# DS90UB933TRTVRQ1.net
KiCad netlist of a schematic drawn in Altium Designer
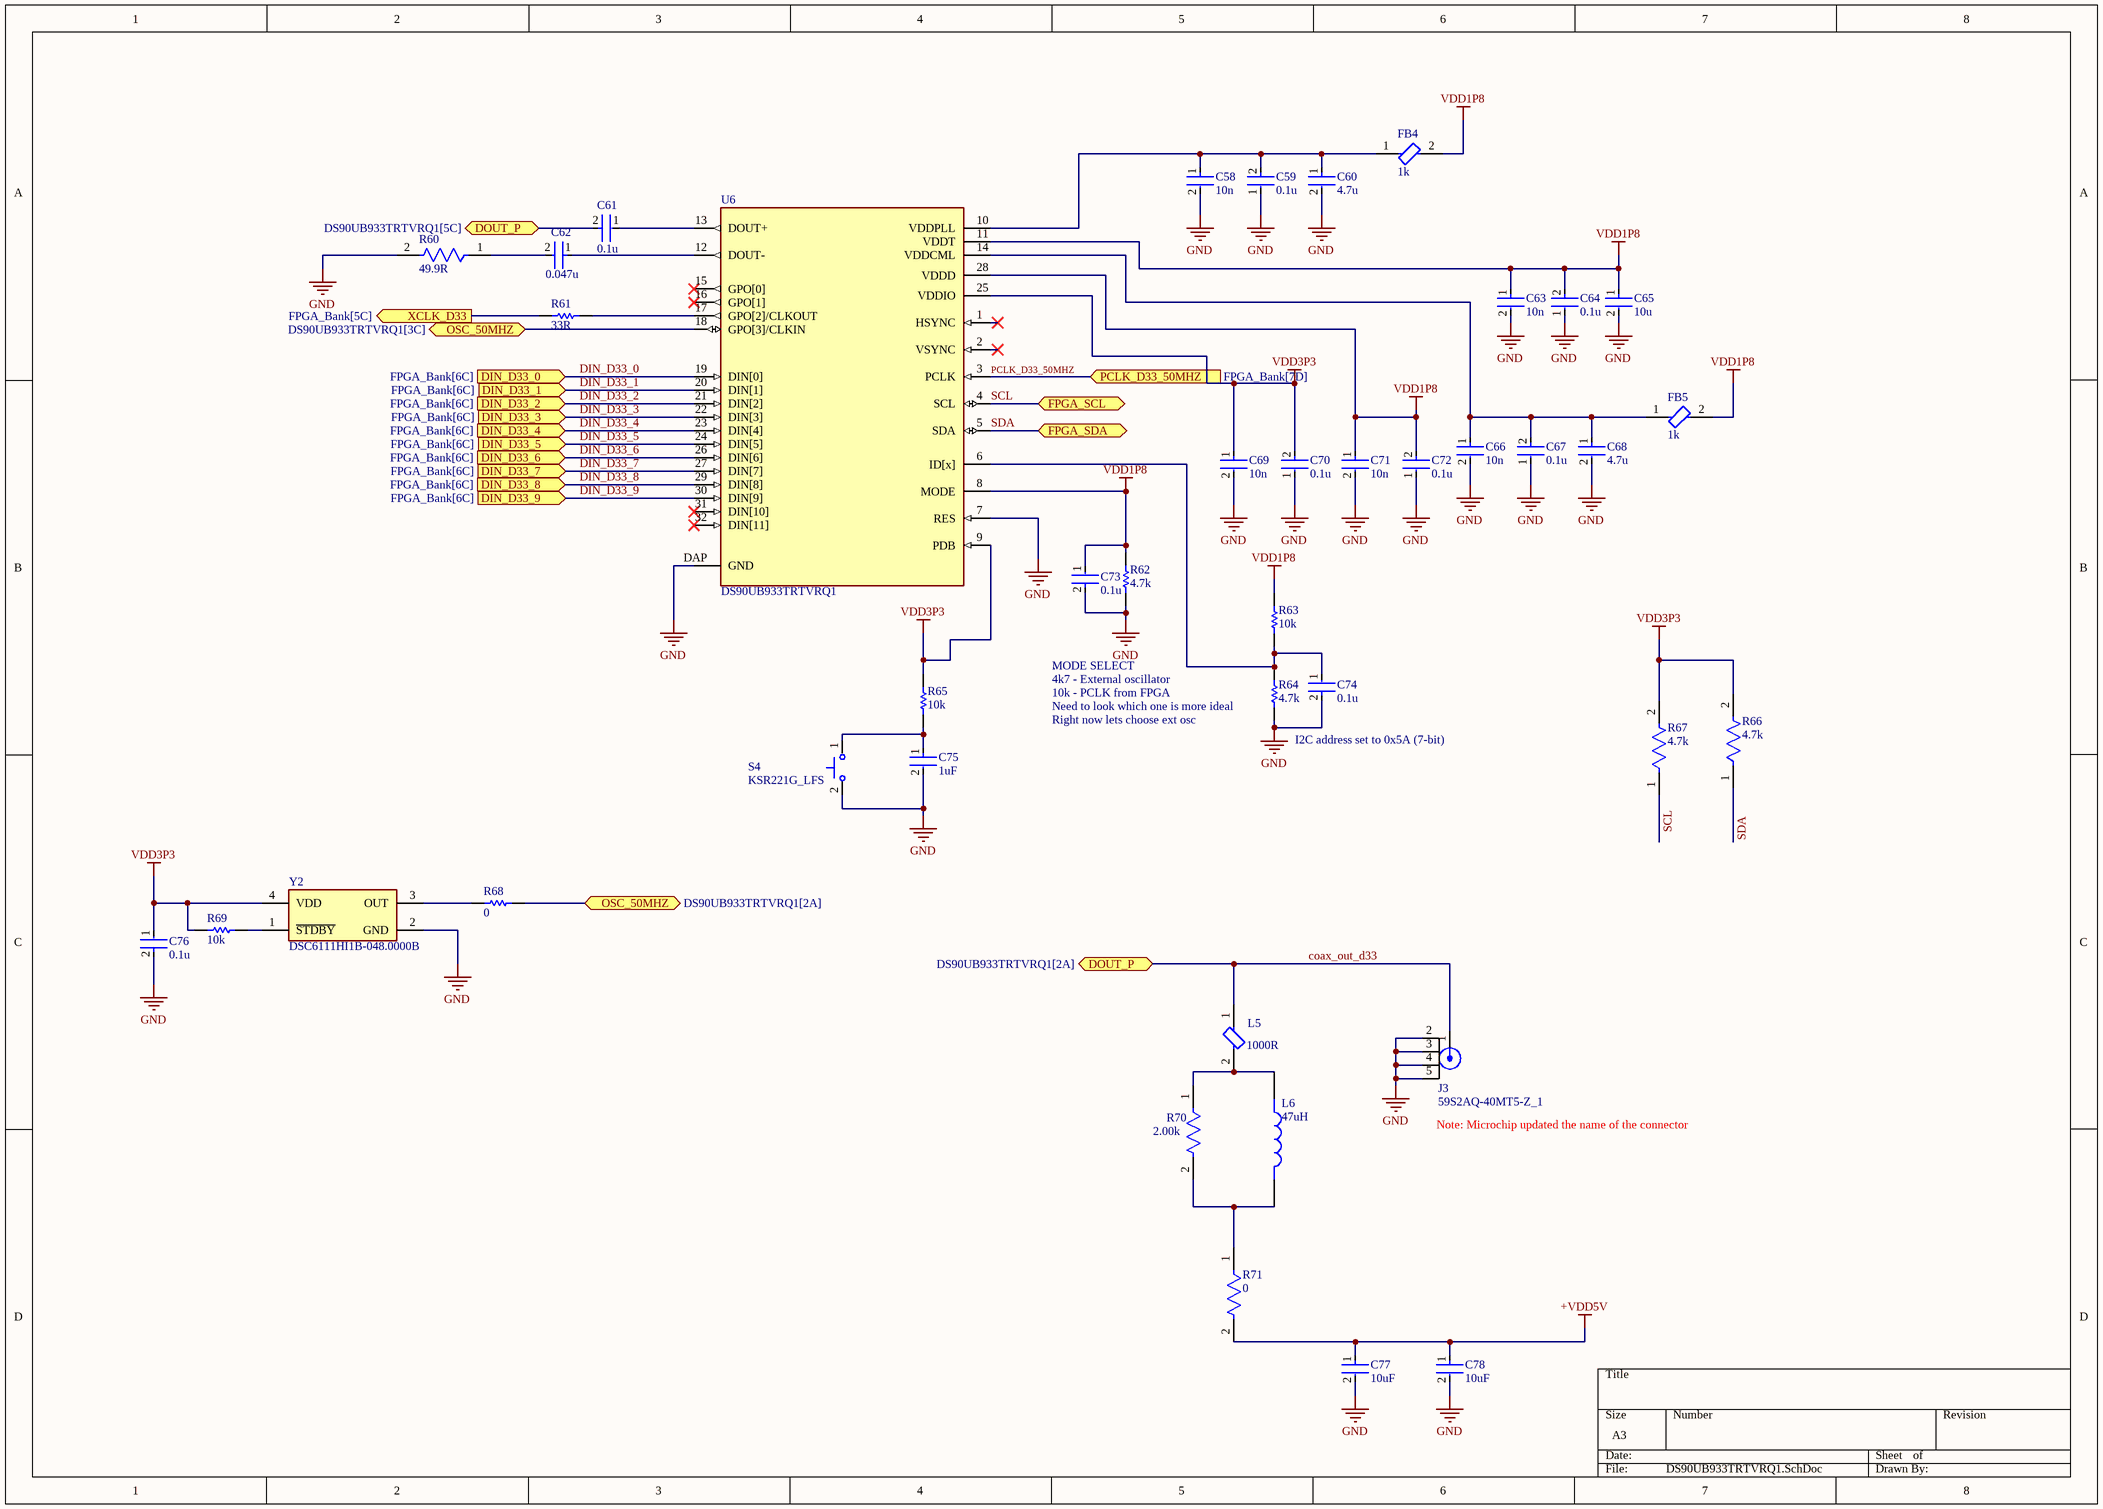
[diagram p0: DS90UB933TRTVRQ1.SchDoc]

(export (version "E")
  (design (tool "Eeschema 10.0.6"))
  (components
    (comp (ref "C58")
      (value "10n")
      (footprint "FP-GCM155-0_05-IPC_C")
      (description "Ceramic Capacitor for Automotive 10nF ±10% 50VDC X7R 0402 Paper T/R")
      (fields (field (name "TOLERANCE") "10%") (field (name "VOLTAGE") "50V"))
      (libsource (lib "Altium Content Vault") (part "02cd4be3c70576c341d710602a673aa"))
    )
    (comp (ref "C59")
      (value "0.1u")
      (footprint "FP-GRM15-MFG")
      (description "CAP CER 0.1UF 16V X7R 0402")
      (fields (field (name "MANUFACTURER PART NUMBER") "GRM155R71C104KA88D") (field (name "TOLERANCE") "10%"))
      (libsource (lib "Altium Content Vault") (part "236180d848d6139a670b325ea6854c9"))
    )
    (comp (ref "C60")
      (value "4.7u")
      (footprint "FP-GRM188-0_15-IPC_C")
      (description "Chip Multilayer Ceramic Capacitors for General Purpose, 0603, 4.7uF, X5R, 15%, 10%, 25V")
      (fields (field (name "VOLTAGE") "25V") (field (name "TOLERANCE") "10%"))
      (libsource (lib "Altium Content Vault") (part "02cd4be3c70576c341d710602a673aa"))
    )
    (comp (ref "C61")
      (value "0.1u")
      (footprint "FP-GRM15-MFG")
      (description "CAP CER 0.1UF 16V X7R 0402")
      (fields (field (name "MANUFACTURER PART NUMBER") "GRM155R71C104KA88D") (field (name "TOLERANCE") "10%"))
      (libsource (lib "Altium Content Vault") (part "236180d848d6139a670b325ea6854c9"))
    )
    (comp (ref "C62")
      (value "0.047u")
      (footprint "FP-C1005-050-0_05-IPC_C")
      (description "Multilayer Ceramic Capacitors 47nF ±10% 50V X7R SMD 0402")
      (fields (field (name "VOLTAGE") "50V") (field (name "TOLERANCE") "10%"))
      (libsource (lib "Altium Content Vault") (part "b4654b650e69147ec39a6b967a45e02"))
    )
    (comp (ref "C63")
      (value "10n")
      (footprint "FP-GCM155-0_05-IPC_C")
      (description "Ceramic Capacitor for Automotive 10nF ±10% 50VDC X7R 0402 Paper T/R")
      (fields (field (name "TOLERANCE") "10%") (field (name "VOLTAGE") "50V"))
      (libsource (lib "Altium Content Vault") (part "02cd4be3c70576c341d710602a673aa"))
    )
    (comp (ref "C64")
      (value "0.1u")
      (footprint "FP-GRM15-MFG")
      (description "CAP CER 0.1UF 16V X7R 0402")
      (fields (field (name "MANUFACTURER PART NUMBER") "GRM155R71C104KA88D") (field (name "TOLERANCE") "10%"))
      (libsource (lib "Altium Content Vault") (part "236180d848d6139a670b325ea6854c9"))
    )
    (comp (ref "C65")
      (value "10u")
      (footprint "FP-GRM188-0_2-MFG")
      (description "Chip Multilayer Ceramic Capacitors for General Purpose, 0603, 10uF, X5R, 15%, 20%, 25V")
      (fields (field (name "TOLERANCE") "20%") (field (name "VOLTAGE") "25V"))
      (libsource (lib "Altium Content Vault") (part "11868f565c42a9108669ba33697ecf6"))
    )
    (comp (ref "C66")
      (value "10n")
      (footprint "FP-GCM155-0_05-IPC_C")
      (description "Ceramic Capacitor for Automotive 10nF ±10% 50VDC X7R 0402 Paper T/R")
      (fields (field (name "TOLERANCE") "10%") (field (name "VOLTAGE") "50V"))
      (libsource (lib "Altium Content Vault") (part "02cd4be3c70576c341d710602a673aa"))
    )
    (comp (ref "C67")
      (value "0.1u")
      (footprint "FP-GRM15-MFG")
      (description "CAP CER 0.1UF 16V X7R 0402")
      (fields (field (name "MANUFACTURER PART NUMBER") "GRM155R71C104KA88D") (field (name "TOLERANCE") "10%"))
      (libsource (lib "Altium Content Vault") (part "236180d848d6139a670b325ea6854c9"))
    )
    (comp (ref "C68")
      (value "4.7u")
      (footprint "FP-GRM188-0_15-IPC_C")
      (description "Chip Multilayer Ceramic Capacitors for General Purpose, 0603, 4.7uF, X5R, 15%, 10%, 25V")
      (fields (field (name "VOLTAGE") "25V") (field (name "TOLERANCE") "10%"))
      (libsource (lib "Altium Content Vault") (part "02cd4be3c70576c341d710602a673aa"))
    )
    (comp (ref "C69")
      (value "10n")
      (footprint "FP-GCM155-0_05-IPC_C")
      (description "Ceramic Capacitor for Automotive 10nF ±10% 50VDC X7R 0402 Paper T/R")
      (fields (field (name "TOLERANCE") "10%") (field (name "VOLTAGE") "50V"))
      (libsource (lib "Altium Content Vault") (part "02cd4be3c70576c341d710602a673aa"))
    )
    (comp (ref "C70")
      (value "0.1u")
      (footprint "FP-GRM15-MFG")
      (description "CAP CER 0.1UF 16V X7R 0402")
      (fields (field (name "MANUFACTURER PART NUMBER") "GRM155R71C104KA88D") (field (name "TOLERANCE") "10%"))
      (libsource (lib "Altium Content Vault") (part "236180d848d6139a670b325ea6854c9"))
    )
    (comp (ref "C71")
      (value "10n")
      (footprint "FP-GCM155-0_05-IPC_C")
      (description "Ceramic Capacitor for Automotive 10nF ±10% 50VDC X7R 0402 Paper T/R")
      (fields (field (name "TOLERANCE") "10%") (field (name "VOLTAGE") "50V"))
      (libsource (lib "Altium Content Vault") (part "02cd4be3c70576c341d710602a673aa"))
    )
    (comp (ref "C72")
      (value "0.1u")
      (footprint "FP-GRM15-MFG")
      (description "CAP CER 0.1UF 16V X7R 0402")
      (fields (field (name "MANUFACTURER PART NUMBER") "GRM155R71C104KA88D") (field (name "TOLERANCE") "10%"))
      (libsource (lib "Altium Content Vault") (part "236180d848d6139a670b325ea6854c9"))
    )
    (comp (ref "C73")
      (value "0.1u")
      (footprint "FP-GRM15-MFG")
      (description "CAP CER 0.1UF 16V X7R 0402")
      (fields (field (name "MANUFACTURER PART NUMBER") "GRM155R71C104KA88D") (field (name "TOLERANCE") "10%"))
      (libsource (lib "Altium Content Vault") (part "236180d848d6139a670b325ea6854c9"))
    )
    (comp (ref "C74")
      (value "0.1u")
      (footprint "FP-GRM15-MFG")
      (description "CAP CER 0.1UF 16V X7R 0402")
      (fields (field (name "MANUFACTURER PART NUMBER") "GRM155R71C104KA88D") (field (name "TOLERANCE") "10%"))
      (libsource (lib "Altium Content Vault") (part "236180d848d6139a670b325ea6854c9"))
    )
    (comp (ref "C75")
      (value "1uF")
      (footprint "FP-C1005-050-0_05-IPC_B")
      (description "Multilayer Ceramic Capacitors 1μF ±10% 25V X5R SMD 0402")
      (fields (field (name "TOLERANCE") "10%"))
      (libsource (lib "Altium Content Vault") (part "b4654b650e69147ec39a6b967a45e02"))
    )
    (comp (ref "C76")
      (value "0.1u")
      (footprint "FP-GRM15-MFG")
      (description "CAP CER 0.1UF 16V X7R 0402")
      (fields (field (name "MANUFACTURER PART NUMBER") "GRM155R71C104KA88D") (field (name "TOLERANCE") "10%"))
      (libsource (lib "Altium Content Vault") (part "236180d848d6139a670b325ea6854c9"))
    )
    (comp (ref "C77")
      (value "10uF")
      (footprint "FP-GRM188-0_2-MFG")
      (description "Chip Multilayer Ceramic Capacitors for General Purpose, 0603, 10uF, X5R, 15%, 20%, 25V")
      (fields (field (name "TOLERANCE") "20%") (field (name "VOLTAGE") "25V"))
      (libsource (lib "Altium Content Vault") (part "11868f565c42a9108669ba33697ecf6"))
    )
    (comp (ref "C78")
      (value "10uF")
      (footprint "FP-GRM188-0_2-MFG")
      (description "Chip Multilayer Ceramic Capacitors for General Purpose, 0603, 10uF, X5R, 15%, 20%, 25V")
      (fields (field (name "TOLERANCE") "20%") (field (name "VOLTAGE") "25V"))
      (libsource (lib "Altium Content Vault") (part "11868f565c42a9108669ba33697ecf6"))
    )
    (comp (ref "FB4")
      (value "1k")
      (footprint "FP-BLM15-0_05-IPC_C")
      (description "Chip Ferrite Bead, 0402, 1000Ω @ 100MHz, 1.25Ω, 25%, 250mA")
      (fields (field (name "TOLERANCE") "25%"))
      (libsource (lib "Altium Content Vault") (part "5f30dd21d616792df468990f7003faa"))
    )
    (comp (ref "FB5")
      (value "1k")
      (footprint "FP-BLM15-0_05-IPC_C")
      (description "Chip Ferrite Bead, 0402, 1000Ω @ 100MHz, 1.25Ω, 25%, 250mA")
      (fields (field (name "TOLERANCE") "25%"))
      (libsource (lib "Altium Content Vault") (part "5f30dd21d616792df468990f7003faa"))
    )
    (comp (ref "J3")
      (value "59S2AQ-40MT5-Z_1")
      (footprint "SerDes_Eval_Board_Footprints:ROSENBERGER_59S2AQ-40MT5-Z_1")
      (description "RF Connectors / Coaxial Connectors Plug PC-Board SMD Right AngleZWatrBlue")
      (libsource (lib "SerDes_Eval") (part "59S2AQ-40MT5-Z_1"))
    )
    (comp (ref "L5")
      (value "1000R")
      (footprint "FP-BLM15-0_05-IPC_C")
      (description "Chip Ferrite Bead, 0402, 1000Ω @ 100MHz, 1.25Ω, 25%, 250mA")
      (fields (field (name "TOLERANCE") "25%"))
      (libsource (lib "Altium Content Vault") (part "5f30dd21d616792df468990f7003faa"))
    )
    (comp (ref "L6")
      (value "47uH")
      (footprint "IND_ADL3225V-470MT-TL000")
      (fields (field (name "MP") "ADL3225V-470MT-TL000") (field (name "MF") "{'manufacturer': u'TDK'}"))
      (libsource (lib "SerDes_Eval") (part "ADL3225V-470MT-TL000"))
    )
    (comp (ref "R60")
      (value "49.9R")
      (footprint "FP-CRCW0402-e3-MFG")
      (description "RES Thick Film, 49.9Ω, 1%, 0.063W, 100ppm/°C, 0402")
      (fields (field (name "TOLERANCE") "1%"))
      (libsource (lib "Altium Content Vault") (part "1029c3af85768c4190bb7ad29bc67b5"))
    )
    (comp (ref "R61")
      (value "33R")
      (footprint "RESC1005X40X25ML05T05")
      (fields (field (name "MANUFACTURER") "Vishay Dale") (field (name "PART NUMBER") "CRCW040233R0JNED"))
      (libsource (lib "Altium Content Vault") (part "RES"))
    )
    (comp (ref "R62")
      (value "4.7k")
      (footprint "RESC1005X40X25LL05T05")
      (description "Chip Resistor, 4.7 KOhm, +/- 1%, 0.1 W, -55 to 155 degC, 0402 (1005 Metric), RoHS, Tape and Reel")
      (fields (field (name "TOLERANCE") "1%") (field (name "PARTNUMBER") "ERJ-2RKF4701X"))
      (libsource (lib "Altium Content Vault") (part "RES-2"))
    )
    (comp (ref "R63")
      (value "10k")
      (footprint "RESC1005X40X25ML05T10")
      (fields (field (name "PART NUMBER") "CRCW040210K0FKEDHP") (field (name "MANUFACTURER") "Vishay Dale"))
      (libsource (lib "Altium Content Vault") (part "RES"))
    )
    (comp (ref "R64")
      (value "4.7k")
      (footprint "RESC1005X40X25LL05T05")
      (description "Chip Resistor, 4.7 KOhm, +/- 1%, 0.1 W, -55 to 155 degC, 0402 (1005 Metric), RoHS, Tape and Reel")
      (fields (field (name "TOLERANCE") "1%") (field (name "PARTNUMBER") "ERJ-2RKF4701X"))
      (libsource (lib "Altium Content Vault") (part "RES-2"))
    )
    (comp (ref "R65")
      (value "10k")
      (footprint "RESC1005X40X25ML05T10")
      (fields (field (name "PART NUMBER") "CRCW040210K0FKEDHP") (field (name "MANUFACTURER") "Vishay Dale"))
      (libsource (lib "Altium Content Vault") (part "RES"))
    )
    (comp (ref "R66")
      (value "4.7k")
      (footprint "FP-CRCW0402-e3-IPC_A")
      (description "RES Thick Film, 4.7kΩ, 5%, 0.063W, 200ppm/°C, 0402")
      (fields (field (name "TOLERANCE") "5%"))
      (libsource (lib "Altium Content Vault") (part "1029c3af85768c4190bb7ad29bc67b5"))
    )
    (comp (ref "R67")
      (value "4.7k")
      (footprint "FP-CRCW0402-e3-IPC_A")
      (description "RES Thick Film, 4.7kΩ, 5%, 0.063W, 200ppm/°C, 0402")
      (fields (field (name "TOLERANCE") "5%"))
      (libsource (lib "Altium Content Vault") (part "1029c3af85768c4190bb7ad29bc67b5"))
    )
    (comp (ref "R68")
      (value "0")
      (footprint "RESC1005X40X25LL05T05")
      (description "Chip Resistor, 0 Ohm, 0.1 W, -55 to 155 degC, 0402 (1005 Metric), RoHS, Tape and Reel")
      (fields (field (name "MANUFACTURER") "Panasonic") (field (name "TOLERANCE") "5%"))
      (libsource (lib "Altium Content Vault") (part "RES-2"))
    )
    (comp (ref "R69")
      (value "10k")
      (footprint "RESC1005X40X25ML05T10")
      (fields (field (name "PART NUMBER") "CRCW040210K0FKEDHP") (field (name "MANUFACTURER") "Vishay Dale"))
      (libsource (lib "Altium Content Vault") (part "RES"))
    )
    (comp (ref "R70")
      (value "2.00k")
      (footprint "FP-CRCW0402-e3-IPC_C")
      (description "RES Thick Film, 0Ω, 0.063W, 0402")
      (fields (field (name "TOLERANCE") "5%"))
      (libsource (lib "Altium Content Vault") (part "1029c3af85768c4190bb7ad29bc67b5"))
    )
    (comp (ref "R71")
      (value "0")
      (footprint "FP-CRCW0402-e3-IPC_C")
      (description "RES Thick Film, 0Ω, 0.063W, 0402")
      (fields (field (name "TOLERANCE") "5%"))
      (libsource (lib "Altium Content Vault") (part "1029c3af85768c4190bb7ad29bc67b5"))
    )
    (comp (ref "S4")
      (value "KSR221G_LFS")
      (footprint "SamacSys:KSR")
      (description "Switch")
      (fields
        (field (name "MANUFACTURER_PART_NUMBER") "KSR221G LFS")
        (field (name "MOUSER PART NUMBER") "611-KSR221G-LFS")
      )
      (libsource (lib "SerDes_Eval") (part "KSR221G_LFS"))
    )
    (comp (ref "U6")
      (value "DS90UB933TRTVRQ1")
      (footprint "FP-RTV0032A-IPC_A")
      (description "IC SERIALIZER FPD-LINK 32WQFN")
      (libsource (lib "SerDes_Eval") (part "CMP-04882-000010-1"))
    )
    (comp (ref "Y2")
      (value "DSC6111HI1B-048.0000B")
      (footprint "SamacSys:DSC6111HI1B0480000B")
      (description "Crystal or Oscillator")
      (libsource (lib "SerDes_Eval") (part "DSC6111HI1B-048.0000B"))
    )
  )
  (nets
    (net (code "1") (name "+VDD5V") (class "Default")
      (node (ref "C77") (pin "1") (pinfunction "1_1") (pintype "passive"))
      (node (ref "C78") (pin "1") (pinfunction "1_1") (pintype "passive"))
      (node (ref "R71") (pin "2") (pinfunction "2_2") (pintype "passive"))
    )
    (net (code "2") (name "/DIN_D33_0") (class "Default")
      (node (ref "U6") (pin "19") (pinfunction "DIN[0]_19") (pintype "input"))
    )
    (net (code "3") (name "/DIN_D33_1") (class "Default")
      (node (ref "U6") (pin "20") (pinfunction "DIN[1]_20") (pintype "input"))
    )
    (net (code "4") (name "/DIN_D33_2") (class "Default")
      (node (ref "U6") (pin "21") (pinfunction "DIN[2]_21") (pintype "input"))
    )
    (net (code "5") (name "/DIN_D33_3") (class "Default")
      (node (ref "U6") (pin "22") (pinfunction "DIN[3]_22") (pintype "input"))
    )
    (net (code "6") (name "/DIN_D33_4") (class "Default")
      (node (ref "U6") (pin "23") (pinfunction "DIN[4]_23") (pintype "input"))
    )
    (net (code "7") (name "/DIN_D33_5") (class "Default")
      (node (ref "U6") (pin "24") (pinfunction "DIN[5]_24") (pintype "input"))
    )
    (net (code "8") (name "/DIN_D33_6") (class "Default")
      (node (ref "U6") (pin "26") (pinfunction "DIN[6]_26") (pintype "input"))
    )
    (net (code "9") (name "/DIN_D33_7") (class "Default")
      (node (ref "U6") (pin "27") (pinfunction "DIN[7]_27") (pintype "input"))
    )
    (net (code "10") (name "/DIN_D33_8") (class "Default")
      (node (ref "U6") (pin "29") (pinfunction "DIN[8]_29") (pintype "input"))
    )
    (net (code "11") (name "/DIN_D33_9") (class "Default")
      (node (ref "U6") (pin "30") (pinfunction "DIN[9]_30") (pintype "input"))
    )
    (net (code "12") (name "/OSC_50MHZ") (class "Default")
      (node (ref "R68") (pin "2") (pinfunction "2_2") (pintype "passive"))
      (node (ref "U6") (pin "18") (pinfunction "GPO[3]/CLKIN_18") (pintype "bidirectional"))
    )
    (net (code "13") (name "/PCLK_D33_50MHZ") (class "Default")
      (node (ref "U6") (pin "3") (pinfunction "PCLK_3") (pintype "input"))
    )
    (net (code "14") (name "/SCL") (class "Default")
      (node (ref "R67") (pin "1") (pinfunction "1_1") (pintype "passive"))
      (node (ref "U6") (pin "4") (pinfunction "SCL_4") (pintype "bidirectional"))
    )
    (net (code "15") (name "/SDA") (class "Default")
      (node (ref "R66") (pin "1") (pinfunction "1_1") (pintype "passive"))
      (node (ref "U6") (pin "5") (pinfunction "SDA_5") (pintype "bidirectional"))
    )
    (net (code "16") (name "/XCLK_D33") (class "Default")
      (node (ref "R61") (pin "1") (pinfunction "1_1") (pintype "passive"))
    )
    (net (code "17") (name "/coax_out_d33") (class "Default")
      (node (ref "C61") (pin "2") (pinfunction "2_2") (pintype "passive"))
      (node (ref "J3") (pin "1") (pinfunction "1_1") (pintype "passive"))
      (node (ref "L5") (pin "1") (pinfunction "1_1") (pintype "passive"))
    )
    (net (code "18") (name "GND") (class "Default")
      (node (ref "C58") (pin "2") (pinfunction "2_2") (pintype "passive"))
      (node (ref "C59") (pin "1") (pinfunction "1_1") (pintype "passive"))
      (node (ref "C60") (pin "2") (pinfunction "2_2") (pintype "passive"))
      (node (ref "C63") (pin "2") (pinfunction "2_2") (pintype "passive"))
      (node (ref "C64") (pin "1") (pinfunction "1_1") (pintype "passive"))
      (node (ref "C65") (pin "2") (pinfunction "2_2") (pintype "passive"))
      (node (ref "C66") (pin "2") (pinfunction "2_2") (pintype "passive"))
      (node (ref "C67") (pin "1") (pinfunction "1_1") (pintype "passive"))
      (node (ref "C68") (pin "2") (pinfunction "2_2") (pintype "passive"))
      (node (ref "C69") (pin "2") (pinfunction "2_2") (pintype "passive"))
      (node (ref "C70") (pin "1") (pinfunction "1_1") (pintype "passive"))
      (node (ref "C71") (pin "2") (pinfunction "2_2") (pintype "passive"))
      (node (ref "C72") (pin "1") (pinfunction "1_1") (pintype "passive"))
      (node (ref "C73") (pin "2") (pinfunction "2_2") (pintype "passive"))
      (node (ref "C74") (pin "2") (pinfunction "2_2") (pintype "passive"))
      (node (ref "C75") (pin "2") (pinfunction "2_2") (pintype "passive"))
      (node (ref "C76") (pin "2") (pinfunction "2_2") (pintype "passive"))
      (node (ref "C77") (pin "2") (pinfunction "2_2") (pintype "passive"))
      (node (ref "C78") (pin "2") (pinfunction "2_2") (pintype "passive"))
      (node (ref "J3") (pin "2") (pinfunction "2_2") (pintype "passive"))
      (node (ref "J3") (pin "3") (pinfunction "3_3") (pintype "passive"))
      (node (ref "J3") (pin "4") (pinfunction "4_4") (pintype "passive"))
      (node (ref "J3") (pin "5") (pinfunction "5_5") (pintype "passive"))
      (node (ref "R60") (pin "2") (pinfunction "2_2") (pintype "passive"))
      (node (ref "R62") (pin "1") (pinfunction "1_1") (pintype "passive"))
      (node (ref "R64") (pin "1") (pinfunction "1_1") (pintype "passive"))
      (node (ref "S4") (pin "2") (pinfunction "2_2") (pintype "passive"))
      (node (ref "U6") (pin "7") (pinfunction "RES_7") (pintype "input"))
      (node (ref "U6") (pin "DAP") (pinfunction "GND_DAP") (pintype "power_in"))
      (node (ref "Y2") (pin "2") (pinfunction "GND_2") (pintype "passive"))
    )
    (net (code "19") (name "Net-(C62-Pad2)") (class "Default")
      (node (ref "C62") (pin "2") (pinfunction "2_2") (pintype "passive"))
      (node (ref "R60") (pin "1") (pinfunction "1_1") (pintype "passive"))
    )
    (net (code "20") (name "Net-(C75-Pad1)") (class "Default")
      (node (ref "C75") (pin "1") (pinfunction "1_1") (pintype "passive"))
      (node (ref "R65") (pin "1") (pinfunction "1_1") (pintype "passive"))
      (node (ref "S4") (pin "1") (pinfunction "1_1") (pintype "passive"))
    )
    (net (code "21") (name "Net-(L5-Pad2)") (class "Default")
      (node (ref "L5") (pin "2") (pinfunction "2_2") (pintype "passive"))
      (node (ref "L6") (pin "1") (pinfunction "1_1") (pintype "passive"))
      (node (ref "R70") (pin "1") (pinfunction "1_1") (pintype "passive"))
    )
    (net (code "22") (name "Net-(L6-Pad2)") (class "Default")
      (node (ref "L6") (pin "2") (pinfunction "2_2") (pintype "passive"))
      (node (ref "R70") (pin "2") (pinfunction "2_2") (pintype "passive"))
      (node (ref "R71") (pin "1") (pinfunction "1_1") (pintype "passive"))
    )
    (net (code "23") (name "Net-(U6-DOUT+)") (class "Default")
      (node (ref "C61") (pin "1") (pinfunction "1_1") (pintype "passive"))
      (node (ref "U6") (pin "13") (pinfunction "DOUT+_13") (pintype "output"))
    )
    (net (code "24") (name "Net-(U6-DOUT-)") (class "Default")
      (node (ref "C62") (pin "1") (pinfunction "1_1") (pintype "passive"))
      (node (ref "U6") (pin "12") (pinfunction "DOUT-_12") (pintype "output"))
    )
    (net (code "25") (name "Net-(U6-GPO[2]{slash}CLKOUT)") (class "Default")
      (node (ref "R61") (pin "2") (pinfunction "2_2") (pintype "passive"))
      (node (ref "U6") (pin "17") (pinfunction "GPO[2]/CLKOUT_17") (pintype "output"))
    )
    (net (code "26") (name "Net-(U6-ID[x])") (class "Default")
      (node (ref "C74") (pin "1") (pinfunction "1_1") (pintype "passive"))
      (node (ref "R63") (pin "1") (pinfunction "1_1") (pintype "passive"))
      (node (ref "R64") (pin "2") (pinfunction "2_2") (pintype "passive"))
      (node (ref "U6") (pin "6") (pinfunction "ID[x]_6") (pintype "passive"))
    )
    (net (code "27") (name "Net-(U6-VDDCML)") (class "Default")
      (node (ref "C66") (pin "1") (pinfunction "1_1") (pintype "passive"))
      (node (ref "C67") (pin "2") (pinfunction "2_2") (pintype "passive"))
      (node (ref "C68") (pin "1") (pinfunction "1_1") (pintype "passive"))
      (node (ref "FB5") (pin "1") (pinfunction "1_1") (pintype "passive"))
      (node (ref "U6") (pin "14") (pinfunction "VDDCML_14") (pintype "power_in"))
    )
    (net (code "28") (name "Net-(U6-VDDPLL)") (class "Default")
      (node (ref "C58") (pin "1") (pinfunction "1_1") (pintype "passive"))
      (node (ref "C59") (pin "2") (pinfunction "2_2") (pintype "passive"))
      (node (ref "C60") (pin "1") (pinfunction "1_1") (pintype "passive"))
      (node (ref "FB4") (pin "1") (pinfunction "1_1") (pintype "passive"))
      (node (ref "U6") (pin "10") (pinfunction "VDDPLL_10") (pintype "power_in"))
    )
    (net (code "29") (name "Net-(Y2-OUT)") (class "Default")
      (node (ref "R68") (pin "1") (pinfunction "1_1") (pintype "passive"))
      (node (ref "Y2") (pin "3") (pinfunction "OUT_3") (pintype "passive"))
    )
    (net (code "30") (name "Net-(Y2-~{STDBY})") (class "Default")
      (node (ref "R69") (pin "1") (pinfunction "1_1") (pintype "passive"))
      (node (ref "Y2") (pin "1") (pinfunction "~{STDBY}_1") (pintype "passive"))
    )
    (net (code "31") (name "VDD1P8") (class "Default")
      (node (ref "C63") (pin "1") (pinfunction "1_1") (pintype "passive"))
      (node (ref "C64") (pin "2") (pinfunction "2_2") (pintype "passive"))
      (node (ref "C65") (pin "1") (pinfunction "1_1") (pintype "passive"))
      (node (ref "C71") (pin "1") (pinfunction "1_1") (pintype "passive"))
      (node (ref "C72") (pin "2") (pinfunction "2_2") (pintype "passive"))
      (node (ref "C73") (pin "1") (pinfunction "1_1") (pintype "passive"))
      (node (ref "FB4") (pin "2") (pinfunction "2_2") (pintype "passive"))
      (node (ref "FB5") (pin "2") (pinfunction "2_2") (pintype "passive"))
      (node (ref "R62") (pin "2") (pinfunction "2_2") (pintype "passive"))
      (node (ref "R63") (pin "2") (pinfunction "2_2") (pintype "passive"))
      (node (ref "U6") (pin "11") (pinfunction "VDDT_11") (pintype "power_in"))
      (node (ref "U6") (pin "28") (pinfunction "VDDD_28") (pintype "power_in"))
      (node (ref "U6") (pin "8") (pinfunction "MODE_8") (pintype "passive"))
    )
    (net (code "32") (name "VDD3P3") (class "Default")
      (node (ref "C69") (pin "1") (pinfunction "1_1") (pintype "passive"))
      (node (ref "C70") (pin "2") (pinfunction "2_2") (pintype "passive"))
      (node (ref "C76") (pin "1") (pinfunction "1_1") (pintype "passive"))
      (node (ref "R65") (pin "2") (pinfunction "2_2") (pintype "passive"))
      (node (ref "R66") (pin "2") (pinfunction "2_2") (pintype "passive"))
      (node (ref "R67") (pin "2") (pinfunction "2_2") (pintype "passive"))
      (node (ref "R69") (pin "2") (pinfunction "2_2") (pintype "passive"))
      (node (ref "U6") (pin "25") (pinfunction "VDDIO_25") (pintype "power_in"))
      (node (ref "U6") (pin "9") (pinfunction "PDB_9") (pintype "input"))
      (node (ref "Y2") (pin "4") (pinfunction "VDD_4") (pintype "passive"))
    )
    (net (code "33") (name "unconnected-(U6-DIN[10]-Pad31)") (class "Default")
      (node (ref "U6") (pin "31") (pinfunction "DIN[10]_31") (pintype "input+no_connect"))
    )
    (net (code "34") (name "unconnected-(U6-DIN[11]-Pad32)") (class "Default")
      (node (ref "U6") (pin "32") (pinfunction "DIN[11]_32") (pintype "input+no_connect"))
    )
    (net (code "35") (name "unconnected-(U6-GPO[0]-Pad15)") (class "Default")
      (node (ref "U6") (pin "15") (pinfunction "GPO[0]_15") (pintype "output+no_connect"))
    )
    (net (code "36") (name "unconnected-(U6-GPO[1]-Pad16)") (class "Default")
      (node (ref "U6") (pin "16") (pinfunction "GPO[1]_16") (pintype "output+no_connect"))
    )
    (net (code "37") (name "unconnected-(U6-HSYNC-Pad1)") (class "Default")
      (node (ref "U6") (pin "1") (pinfunction "HSYNC_1") (pintype "input+no_connect"))
    )
    (net (code "38") (name "unconnected-(U6-VSYNC-Pad2)") (class "Default")
      (node (ref "U6") (pin "2") (pinfunction "VSYNC_2") (pintype "input+no_connect"))
    )
  )
)
